# besc_drive_sch.net
KiCad netlist of a schematic drawn in Altium Designer
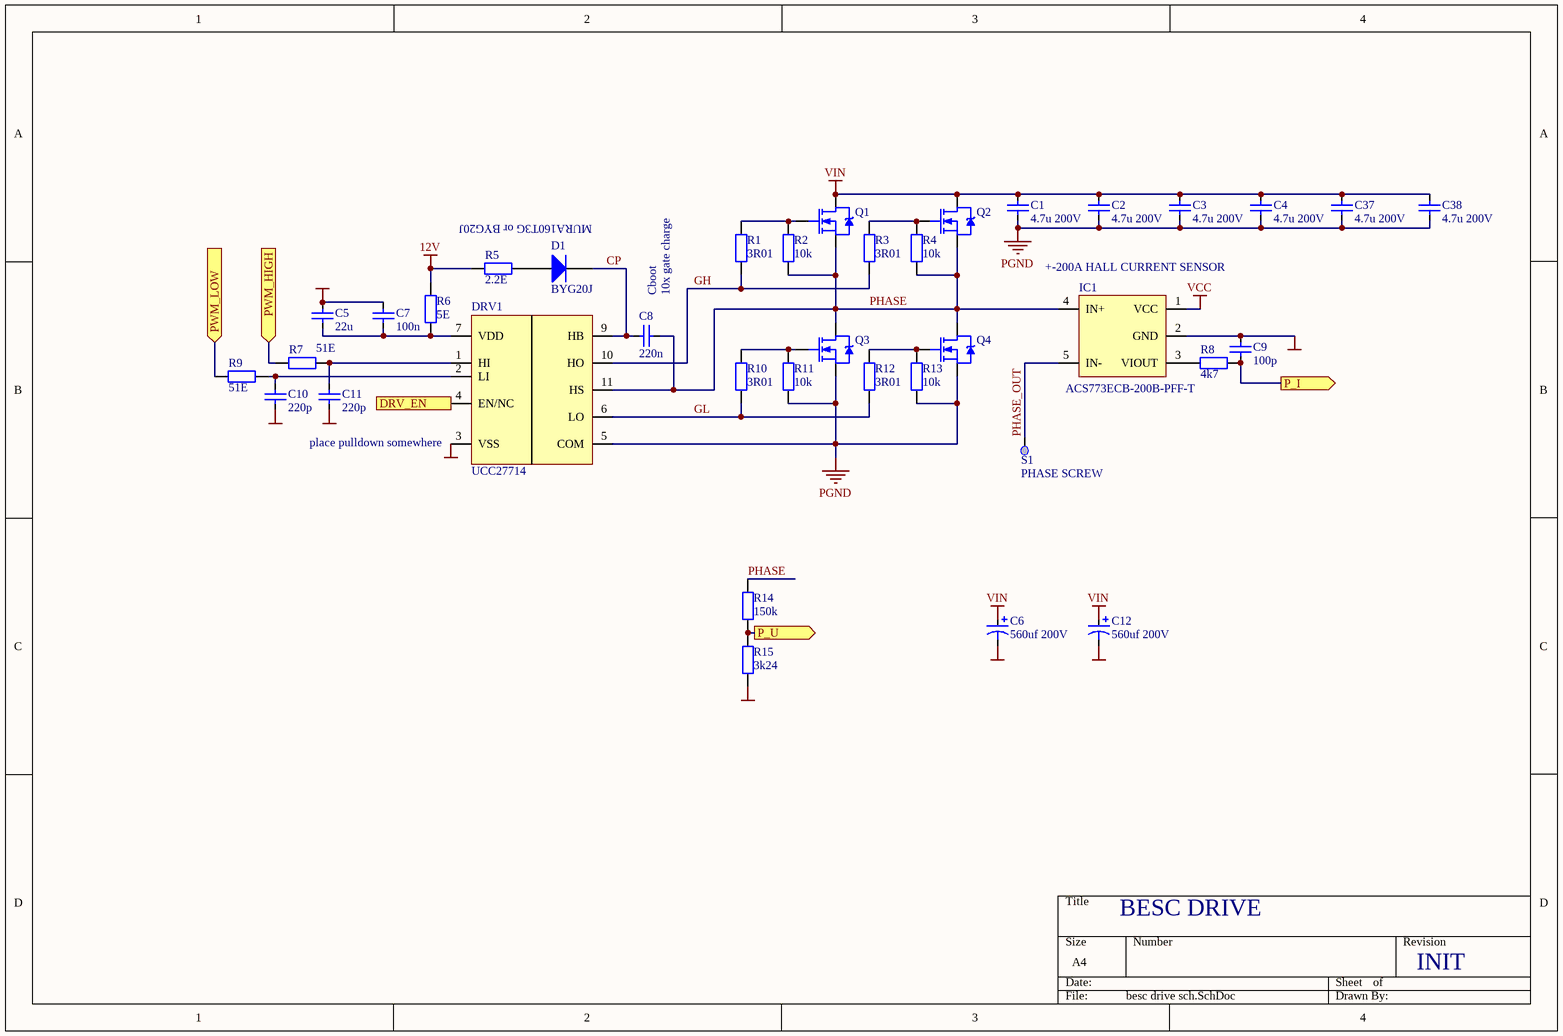
[diagram p0: besc drive sch.SchDoc]

(export (version "E")
  (design (tool "Eeschema 10.0.6"))
  (components
    (comp (ref "C1")
      (value "4.7u 200V")
      (footprint "CAP 2220/5650 3.3MM")
      (description "Capacitor")
      (fields (field (name "PUBLISHER") "Altium Limited"))
      (libsource (lib "Miscellaneous Devices") (part "Cap"))
    )
    (comp (ref "C2")
      (value "4.7u 200V")
      (footprint "CAP 2220/5650 3.3MM")
      (description "Capacitor")
      (fields (field (name "PUBLISHER") "Altium Limited"))
      (libsource (lib "Miscellaneous Devices") (part "Cap"))
    )
    (comp (ref "C3")
      (value "4.7u 200V")
      (footprint "CAP 2220/5650 3.3MM")
      (description "Capacitor")
      (fields (field (name "PUBLISHER") "Altium Limited"))
      (libsource (lib "Miscellaneous Devices") (part "Cap"))
    )
    (comp (ref "C4")
      (value "4.7u 200V")
      (footprint "CAP 2220/5650 3.3MM")
      (description "Capacitor")
      (fields (field (name "PUBLISHER") "Altium Limited"))
      (libsource (lib "Miscellaneous Devices") (part "Cap"))
    )
    (comp (ref "C5")
      (value "22u")
      (footprint "0805")
      (description "Capacitor")
      (fields (field (name "PUBLISHER") "Altium Limited"))
      (libsource (lib "Miscellaneous Devices") (part "Cap"))
    )
    (comp (ref "C6")
      (value "560uf 200V")
      (footprint "ELKO_18x40_90deg")
      (description "Polarized Capacitor (Radial)")
      (fields (field (name "PUBLISHER") "Altium Limited"))
      (libsource (lib "Miscellaneous Devices") (part "Cap Pol1"))
    )
    (comp (ref "C7")
      (value "100n")
      (footprint "0603")
      (description "Capacitor")
      (fields (field (name "PUBLISHER") "Altium Limited"))
      (libsource (lib "Miscellaneous Devices") (part "Cap"))
    )
    (comp (ref "C8")
      (value "220n")
      (footprint "0603")
      (description "Capacitor")
      (fields (field (name "PUBLISHER") "Altium Limited"))
      (libsource (lib "Miscellaneous Devices") (part "Cap"))
    )
    (comp (ref "C9")
      (value "100p")
      (footprint "0603")
      (description "Capacitor")
      (fields (field (name "PUBLISHER") "Altium Limited"))
      (libsource (lib "Miscellaneous Devices") (part "Cap"))
    )
    (comp (ref "C10")
      (value "220p")
      (footprint "0402")
      (description "Capacitor")
      (fields (field (name "PUBLISHER") "Altium Limited"))
      (libsource (lib "Miscellaneous Devices") (part "Cap"))
    )
    (comp (ref "C11")
      (value "220p")
      (footprint "0402")
      (description "Capacitor")
      (fields (field (name "PUBLISHER") "Altium Limited"))
      (libsource (lib "Miscellaneous Devices") (part "Cap"))
    )
    (comp (ref "C12")
      (value "560uf 200V")
      (footprint "ELKO_18x40_90deg")
      (description "Polarized Capacitor (Radial)")
      (fields (field (name "PUBLISHER") "Altium Limited"))
      (libsource (lib "Miscellaneous Devices") (part "Cap Pol1"))
    )
    (comp (ref "C37")
      (value "4.7u 200V")
      (footprint "CAP 2220/5650 3.3MM")
      (description "Capacitor")
      (fields (field (name "PUBLISHER") "Altium Limited"))
      (libsource (lib "Miscellaneous Devices") (part "Cap"))
    )
    (comp (ref "C38")
      (value "4.7u 200V")
      (footprint "CAP 2220/5650 3.3MM")
      (description "Capacitor")
      (fields (field (name "PUBLISHER") "Altium Limited"))
      (libsource (lib "Miscellaneous Devices") (part "Cap"))
    )
    (comp (ref "D1")
      (value "BYG20J")
      (footprint "DO-214AC")
      (description "High Conductance Fast Diode")
      (fields (field (name "PUBLISHER") "Altium Limited"))
      (libsource (lib "Miscellaneous Devices") (part "Diode 1N4148"))
    )
    (comp (ref "DRV1") (value "UCC27714") (footprint "SOIC14_M") (libsource (lib "moja") (part "UCC27714")))
    (comp (ref "IC1")
      (value "ACS773ECB-200B-PFF-T")
      (footprint "ACS758")
      (libsource (lib "moja") (part "ACS758"))
    )
    (comp (ref "Q1")
      (value "IPB044N15N5")
      (footprint "Dpak-7")
      (description "N-Channel Power MOSFET")
      (fields (field (name "PUBLISHER") "Altium Limited"))
      (libsource (lib "Miscellaneous Devices") (part "NMOS-2"))
    )
    (comp (ref "Q2")
      (value "IPB044N15N5")
      (footprint "Dpak-7")
      (description "N-Channel Power MOSFET")
      (fields (field (name "PUBLISHER") "Altium Limited"))
      (libsource (lib "Miscellaneous Devices") (part "NMOS-2"))
    )
    (comp (ref "Q3")
      (value "IPB044N15N5")
      (footprint "Dpak-7")
      (description "N-Channel Power MOSFET")
      (fields (field (name "PUBLISHER") "Altium Limited"))
      (libsource (lib "Miscellaneous Devices") (part "NMOS-2"))
    )
    (comp (ref "Q4")
      (value "IPB044N15N5")
      (footprint "Dpak-7")
      (description "N-Channel Power MOSFET")
      (fields (field (name "PUBLISHER") "Altium Limited"))
      (libsource (lib "Miscellaneous Devices") (part "NMOS-2"))
    )
    (comp (ref "R1")
      (value "3R01")
      (footprint "0603")
      (description "Resistor")
      (fields (field (name "PUBLISHER") "Altium Limited"))
      (libsource (lib "") (part "Res2_1"))
    )
    (comp (ref "R2")
      (value "10k")
      (footprint "0603")
      (description "Resistor")
      (fields (field (name "PUBLISHER") "Altium Limited"))
      (libsource (lib "") (part "Res2_1"))
    )
    (comp (ref "R3")
      (value "3R01")
      (footprint "0603")
      (description "Resistor")
      (fields (field (name "PUBLISHER") "Altium Limited"))
      (libsource (lib "") (part "Res2_1"))
    )
    (comp (ref "R4")
      (value "10k")
      (footprint "0603")
      (description "Resistor")
      (fields (field (name "PUBLISHER") "Altium Limited"))
      (libsource (lib "") (part "Res2_1"))
    )
    (comp (ref "R5")
      (value "2.2E")
      (footprint "1210")
      (description "Resistor")
      (fields (field (name "PUBLISHER") "Altium Limited"))
      (libsource (lib "Miscellaneous Devices") (part "Res2"))
    )
    (comp (ref "R6")
      (value "5E")
      (footprint "0603")
      (description "Resistor")
      (fields (field (name "PUBLISHER") "Altium Limited"))
      (libsource (lib "") (part "Res2_1"))
    )
    (comp (ref "R7")
      (value "51E")
      (footprint "0402")
      (description "Resistor")
      (fields (field (name "PUBLISHER") "Altium Limited"))
      (libsource (lib "Miscellaneous Devices") (part "Res2"))
    )
    (comp (ref "R8")
      (value "4k7")
      (footprint "0603")
      (description "Resistor")
      (fields (field (name "PUBLISHER") "Altium Limited"))
      (libsource (lib "Miscellaneous Devices") (part "Res2"))
    )
    (comp (ref "R9")
      (value "51E")
      (footprint "0402")
      (description "Resistor")
      (fields (field (name "PUBLISHER") "Altium Limited"))
      (libsource (lib "") (part "Res2_2"))
    )
    (comp (ref "R10")
      (value "3R01")
      (footprint "0603")
      (description "Resistor")
      (fields (field (name "PUBLISHER") "Altium Limited"))
      (libsource (lib "") (part "Res2_1"))
    )
    (comp (ref "R11")
      (value "10k")
      (footprint "0603")
      (description "Resistor")
      (fields (field (name "PUBLISHER") "Altium Limited"))
      (libsource (lib "") (part "Res2_1"))
    )
    (comp (ref "R12")
      (value "3R01")
      (footprint "0603")
      (description "Resistor")
      (fields (field (name "PUBLISHER") "Altium Limited"))
      (libsource (lib "") (part "Res2_1"))
    )
    (comp (ref "R13")
      (value "10k")
      (footprint "0603")
      (description "Resistor")
      (fields (field (name "PUBLISHER") "Altium Limited"))
      (libsource (lib "") (part "Res2_1"))
    )
    (comp (ref "R14")
      (value "150k")
      (footprint "0805")
      (description "250 mW 0805")
      (fields (field (name "PUBLISHER") "Altium Limited"))
      (libsource (lib "") (part "Res2_1"))
    )
    (comp (ref "R15")
      (value "3k24")
      (footprint "0402")
      (description "Resistor")
      (fields (field (name "PUBLISHER") "Altium Limited"))
      (libsource (lib "") (part "Res2_1"))
    )
    (comp (ref "S1")
      (value "PHASE SCREW")
      (footprint "WP-SHFU-M6")
      (description "7461098")
      (libsource (lib "moja") (part "En_pin"))
    )
  )
  (nets
    (net (code "1") (name "/CP") (class "Default")
      (node (ref "C8") (pin "2") (pinfunction "2_2") (pintype "passive"))
      (node (ref "D1") (pin "2") (pinfunction "K_2") (pintype "passive"))
      (node (ref "DRV1") (pin "9") (pinfunction "HB_9") (pintype "passive"))
    )
    (net (code "2") (name "/DRV_EN") (class "Default")
      (node (ref "DRV1") (pin "4") (pinfunction "EN/NC_4") (pintype "passive"))
    )
    (net (code "3") (name "/GH") (class "Default")
      (node (ref "DRV1") (pin "10") (pinfunction "HO_10") (pintype "passive"))
      (node (ref "R1") (pin "2") (pinfunction "2_2") (pintype "passive"))
      (node (ref "R3") (pin "2") (pinfunction "2_2") (pintype "passive"))
    )
    (net (code "4") (name "/GL") (class "Default")
      (node (ref "DRV1") (pin "6") (pinfunction "LO_6") (pintype "passive"))
      (node (ref "R10") (pin "2") (pinfunction "2_2") (pintype "passive"))
      (node (ref "R12") (pin "2") (pinfunction "2_2") (pintype "passive"))
    )
    (net (code "5") (name "/PHASE") (class "Default")
      (node (ref "C8") (pin "1") (pinfunction "1_1") (pintype "passive"))
      (node (ref "DRV1") (pin "11") (pinfunction "HS_11") (pintype "passive"))
      (node (ref "IC1") (pin "4") (pinfunction "IN+_4") (pintype "passive"))
      (node (ref "Q1") (pin "2") (pinfunction "S_2") (pintype "passive"))
      (node (ref "Q2") (pin "2") (pinfunction "S_2") (pintype "passive"))
      (node (ref "Q3") (pin "3") (pinfunction "D_3") (pintype "passive"))
      (node (ref "Q4") (pin "3") (pinfunction "D_3") (pintype "passive"))
      (node (ref "R14") (pin "1") (pinfunction "1_1") (pintype "passive"))
      (node (ref "R2") (pin "2") (pinfunction "2_2") (pintype "passive"))
      (node (ref "R4") (pin "2") (pinfunction "2_2") (pintype "passive"))
    )
    (net (code "6") (name "/PHASE_OUT") (class "Default")
      (node (ref "IC1") (pin "5") (pinfunction "IN-_5") (pintype "passive"))
      (node (ref "S1") (pin "1") (pinfunction "1_1") (pintype "passive"))
    )
    (net (code "7") (name "/PWM_HIGH") (class "Default")
      (node (ref "R7") (pin "2") (pinfunction "2_2") (pintype "passive"))
    )
    (net (code "8") (name "/PWM_LOW") (class "Default")
      (node (ref "R9") (pin "1") (pinfunction "1_1") (pintype "passive"))
    )
    (net (code "9") (name "/P_I") (class "Default")
      (node (ref "C9") (pin "1") (pinfunction "1_1") (pintype "passive"))
      (node (ref "R8") (pin "1") (pinfunction "1_1") (pintype "passive"))
    )
    (net (code "10") (name "/P_U") (class "Default")
      (node (ref "R14") (pin "2") (pinfunction "2_2") (pintype "passive"))
      (node (ref "R15") (pin "1") (pinfunction "1_1") (pintype "passive"))
    )
    (net (code "11") (name "12V") (class "Default")
      (node (ref "R5") (pin "2") (pinfunction "2_2") (pintype "passive"))
      (node (ref "R6") (pin "1") (pinfunction "1_1") (pintype "passive"))
    )
    (net (code "12") (name "LGND") (class "Default")
      (node (ref "C10") (pin "2") (pinfunction "2_2") (pintype "passive"))
      (node (ref "C11") (pin "2") (pinfunction "2_2") (pintype "passive"))
      (node (ref "C5") (pin "2") (pinfunction "2_2") (pintype "passive"))
      (node (ref "C7") (pin "2") (pinfunction "2_2") (pintype "passive"))
      (node (ref "C9") (pin "2") (pinfunction "2_2") (pintype "passive"))
      (node (ref "DRV1") (pin "3") (pinfunction "VSS_3") (pintype "passive"))
      (node (ref "IC1") (pin "2") (pinfunction "GND_2") (pintype "passive"))
      (node (ref "R15") (pin "2") (pinfunction "2_2") (pintype "passive"))
    )
    (net (code "13") (name "Net-(D1-A)") (class "Default")
      (node (ref "D1") (pin "1") (pinfunction "A_1") (pintype "passive"))
      (node (ref "R5") (pin "1") (pinfunction "1_1") (pintype "passive"))
    )
    (net (code "14") (name "Net-(DRV1-HI)") (class "Default")
      (node (ref "C11") (pin "1") (pinfunction "1_1") (pintype "passive"))
      (node (ref "DRV1") (pin "1") (pinfunction "HI_1") (pintype "passive"))
      (node (ref "R7") (pin "1") (pinfunction "1_1") (pintype "passive"))
    )
    (net (code "15") (name "Net-(DRV1-LI)") (class "Default")
      (node (ref "C10") (pin "1") (pinfunction "1_1") (pintype "passive"))
      (node (ref "DRV1") (pin "2") (pinfunction "LI_2") (pintype "passive"))
      (node (ref "R9") (pin "2") (pinfunction "2_2") (pintype "passive"))
    )
    (net (code "16") (name "Net-(DRV1-VDD)") (class "Default")
      (node (ref "C5") (pin "1") (pinfunction "1_1") (pintype "passive"))
      (node (ref "C7") (pin "1") (pinfunction "1_1") (pintype "passive"))
      (node (ref "DRV1") (pin "7") (pinfunction "VDD_7") (pintype "passive"))
      (node (ref "R6") (pin "2") (pinfunction "2_2") (pintype "passive"))
    )
    (net (code "17") (name "Net-(IC1-VIOUT)") (class "Default")
      (node (ref "IC1") (pin "3") (pinfunction "VIOUT_3") (pintype "passive"))
      (node (ref "R8") (pin "2") (pinfunction "2_2") (pintype "passive"))
    )
    (net (code "18") (name "Net-(Q1-G)") (class "Default")
      (node (ref "Q1") (pin "1") (pinfunction "G_1") (pintype "passive"))
      (node (ref "R1") (pin "1") (pinfunction "1_1") (pintype "passive"))
      (node (ref "R2") (pin "1") (pinfunction "1_1") (pintype "passive"))
    )
    (net (code "19") (name "Net-(Q2-G)") (class "Default")
      (node (ref "Q2") (pin "1") (pinfunction "G_1") (pintype "passive"))
      (node (ref "R3") (pin "1") (pinfunction "1_1") (pintype "passive"))
      (node (ref "R4") (pin "1") (pinfunction "1_1") (pintype "passive"))
    )
    (net (code "20") (name "Net-(Q3-G)") (class "Default")
      (node (ref "Q3") (pin "1") (pinfunction "G_1") (pintype "passive"))
      (node (ref "R10") (pin "1") (pinfunction "1_1") (pintype "passive"))
      (node (ref "R11") (pin "1") (pinfunction "1_1") (pintype "passive"))
    )
    (net (code "21") (name "Net-(Q4-G)") (class "Default")
      (node (ref "Q4") (pin "1") (pinfunction "G_1") (pintype "passive"))
      (node (ref "R12") (pin "1") (pinfunction "1_1") (pintype "passive"))
      (node (ref "R13") (pin "1") (pinfunction "1_1") (pintype "passive"))
    )
    (net (code "22") (name "PGND") (class "Default")
      (node (ref "C1") (pin "1") (pinfunction "1_1") (pintype "passive"))
      (node (ref "C12") (pin "2") (pinfunction "2_2") (pintype "passive"))
      (node (ref "C2") (pin "1") (pinfunction "1_1") (pintype "passive"))
      (node (ref "C3") (pin "1") (pinfunction "1_1") (pintype "passive"))
      (node (ref "C37") (pin "1") (pinfunction "1_1") (pintype "passive"))
      (node (ref "C38") (pin "1") (pinfunction "1_1") (pintype "passive"))
      (node (ref "C4") (pin "1") (pinfunction "1_1") (pintype "passive"))
      (node (ref "C6") (pin "2") (pinfunction "2_2") (pintype "passive"))
      (node (ref "DRV1") (pin "5") (pinfunction "COM_5") (pintype "passive"))
      (node (ref "Q3") (pin "2") (pinfunction "S_2") (pintype "passive"))
      (node (ref "Q4") (pin "2") (pinfunction "S_2") (pintype "passive"))
      (node (ref "R11") (pin "2") (pinfunction "2_2") (pintype "passive"))
      (node (ref "R13") (pin "2") (pinfunction "2_2") (pintype "passive"))
    )
    (net (code "23") (name "VCC") (class "Default")
      (node (ref "IC1") (pin "1") (pinfunction "VCC_1") (pintype "passive"))
    )
    (net (code "24") (name "VIN") (class "Default")
      (node (ref "C1") (pin "2") (pinfunction "2_2") (pintype "passive"))
      (node (ref "C12") (pin "1") (pinfunction "1_1") (pintype "passive"))
      (node (ref "C2") (pin "2") (pinfunction "2_2") (pintype "passive"))
      (node (ref "C3") (pin "2") (pinfunction "2_2") (pintype "passive"))
      (node (ref "C37") (pin "2") (pinfunction "2_2") (pintype "passive"))
      (node (ref "C38") (pin "2") (pinfunction "2_2") (pintype "passive"))
      (node (ref "C4") (pin "2") (pinfunction "2_2") (pintype "passive"))
      (node (ref "C6") (pin "1") (pinfunction "1_1") (pintype "passive"))
      (node (ref "Q1") (pin "3") (pinfunction "D_3") (pintype "passive"))
      (node (ref "Q2") (pin "3") (pinfunction "D_3") (pintype "passive"))
    )
    (net (code "25") (name "unconnected-(DRV1-NC-Pad8)") (class "Default")
      (node (ref "DRV1") (pin "8") (pinfunction "NC_8") (pintype "passive"))
    )
    (net (code "26") (name "unconnected-(DRV1-NC-Pad12)") (class "Default")
      (node (ref "DRV1") (pin "12") (pinfunction "NC_12") (pintype "passive"))
    )
    (net (code "27") (name "unconnected-(DRV1-NC-Pad13)") (class "Default")
      (node (ref "DRV1") (pin "13") (pinfunction "NC_13") (pintype "passive"))
    )
    (net (code "28") (name "unconnected-(DRV1-NC-Pad14)") (class "Default")
      (node (ref "DRV1") (pin "14") (pinfunction "NC_14") (pintype "passive"))
    )
  )
)
